# Gesture.net
KiCad netlist of a schematic drawn in EAGLE
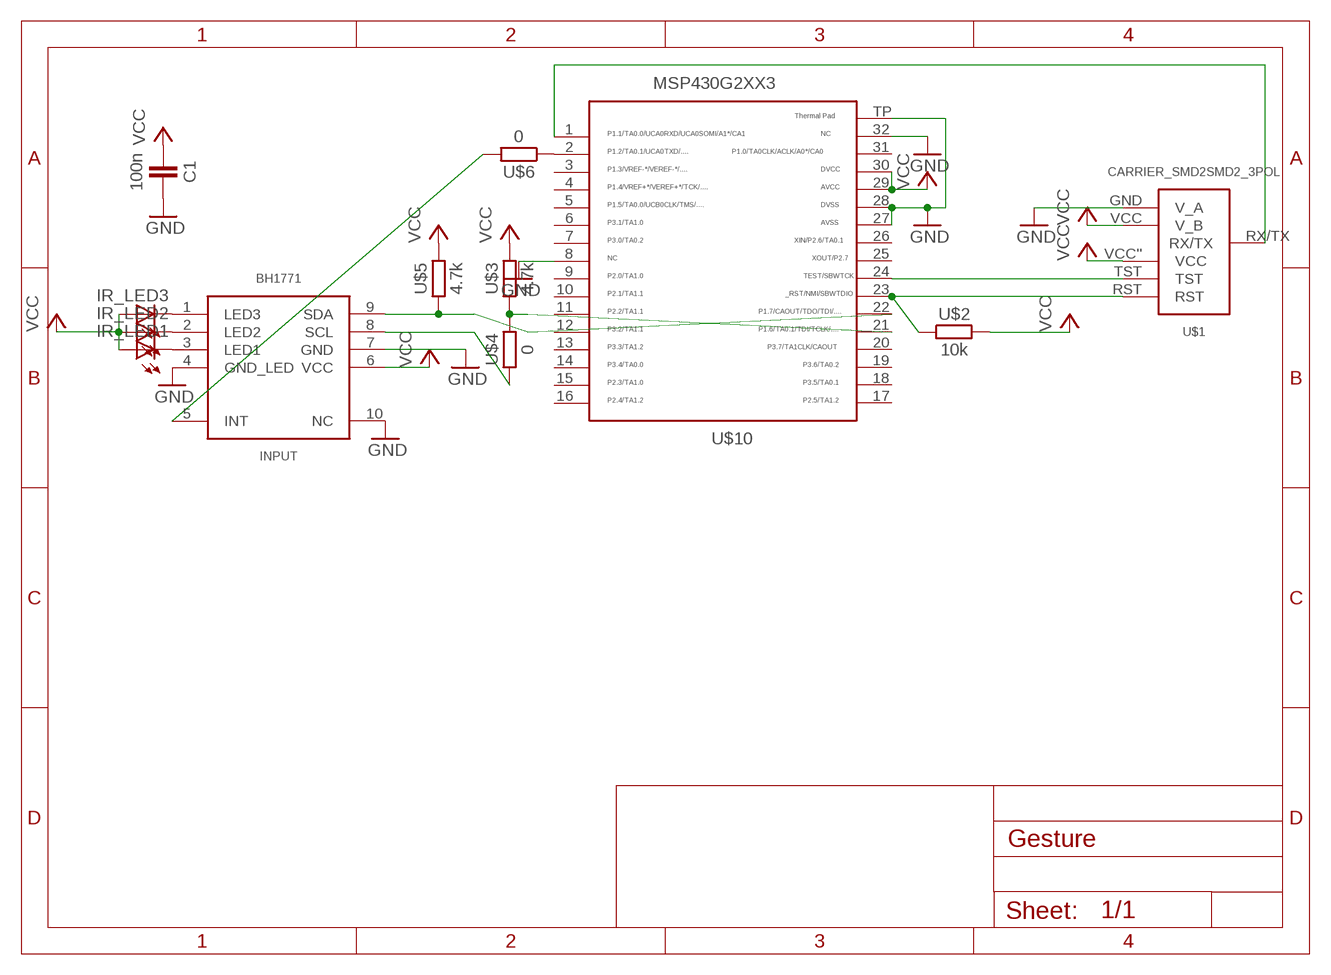
[diagram p0: schematic, sheet 1]

(export (version "E")
  (design (tool "Eeschema 10.0.6"))
  (components
    (comp (ref "C1")
      (value "100n")
      (footprint "eagle-import:603")
      (libsource (lib "eagle-import") (part "CAPACITOR"))
    )
    (comp (ref "INPUT")
      (value "BH1771")
      (footprint "eagle-import:BH1771")
      (libsource (lib "eagle-import") (part "BH1771"))
    )
    (comp (ref "IR_LED1")
      (value "LEDCHIP-LED0603")
      (footprint "eagle-import:CHIP-LED0603")
      (libsource (lib "eagle-import") (part "LEDCHIP-LED0603"))
    )
    (comp (ref "IR_LED2")
      (value "LEDCHIP-LED0603")
      (footprint "eagle-import:CHIP-LED0603")
      (libsource (lib "eagle-import") (part "LEDCHIP-LED0603"))
    )
    (comp (ref "IR_LED3")
      (value "LEDCHIP-LED0603")
      (footprint "eagle-import:CHIP-LED0603")
      (libsource (lib "eagle-import") (part "LEDCHIP-LED0603"))
    )
    (comp (ref "U$1")
      (value "CARRIER_SMD2SMD2_3POL")
      (footprint "eagle-import:CARRIER_SMD2_3POL")
      (libsource (lib "eagle-import") (part "CARRIER_SMD2SMD2_3POL"))
    )
    (comp (ref "U$2")
      (value "10k")
      (footprint "eagle-import:603")
      (libsource (lib "eagle-import") (part "RESISTOR0603"))
    )
    (comp (ref "U$3")
      (value "4.7k")
      (footprint "eagle-import:603")
      (libsource (lib "eagle-import") (part "RESISTOR0603"))
    )
    (comp (ref "U$4")
      (value "0")
      (footprint "eagle-import:603")
      (libsource (lib "eagle-import") (part "RESISTOR0603"))
    )
    (comp (ref "U$5")
      (value "4.7k")
      (footprint "eagle-import:603")
      (libsource (lib "eagle-import") (part "RESISTOR0603"))
    )
    (comp (ref "U$6")
      (value "0")
      (footprint "eagle-import:603")
      (libsource (lib "eagle-import") (part "RESISTOR0603"))
    )
    (comp (ref "U$10")
      (value "MSP430G2553")
      (footprint "eagle-import:QFN32")
      (libsource (lib "eagle-import") (part "MSP430G2553"))
    )
  )
  (nets
    (net (code "1") (name "GND") (class "Default")
      (node (ref "C1") (pin "2") (pinfunction "2_2") (pintype "passive"))
      (node (ref "INPUT") (pin "10") (pinfunction "NC_10") (pintype "bidirectional"))
      (node (ref "INPUT") (pin "4") (pinfunction "GND_LED_4") (pintype "bidirectional"))
      (node (ref "INPUT") (pin "7") (pinfunction "GND_7") (pintype "bidirectional"))
      (node (ref "U$1") (pin "GND") (pinfunction "V_A_GND") (pintype "bidirectional"))
      (node (ref "U$10") (pin "27") (pinfunction "27_27") (pintype "bidirectional"))
      (node (ref "U$10") (pin "28") (pinfunction "28_28") (pintype "bidirectional"))
      (node (ref "U$10") (pin "32") (pinfunction "32_32") (pintype "bidirectional"))
      (node (ref "U$10") (pin "8") (pinfunction "8_8") (pintype "bidirectional"))
      (node (ref "U$10") (pin "TP") (pinfunction "TP_TP") (pintype "bidirectional"))
    )
    (net (code "2") (name "Net-(INPUT-INT)") (class "Default")
      (node (ref "INPUT") (pin "5") (pinfunction "INT_5") (pintype "bidirectional"))
      (node (ref "U$6") (pin "2") (pinfunction "2_2") (pintype "passive"))
    )
    (net (code "3") (name "Net-(INPUT-LED1)") (class "Default")
      (node (ref "INPUT") (pin "3") (pinfunction "LED1_3") (pintype "bidirectional"))
      (node (ref "IR_LED1") (pin "C") (pinfunction "C_C") (pintype "passive"))
    )
    (net (code "4") (name "Net-(INPUT-LED2)") (class "Default")
      (node (ref "INPUT") (pin "2") (pinfunction "LED2_2") (pintype "bidirectional"))
      (node (ref "IR_LED2") (pin "C") (pinfunction "C_C") (pintype "passive"))
    )
    (net (code "5") (name "Net-(INPUT-LED3)") (class "Default")
      (node (ref "INPUT") (pin "1") (pinfunction "LED3_1") (pintype "bidirectional"))
      (node (ref "IR_LED3") (pin "C") (pinfunction "C_C") (pintype "passive"))
    )
    (net (code "6") (name "Net-(INPUT-SCL)") (class "Default")
      (node (ref "INPUT") (pin "8") (pinfunction "SCL_8") (pintype "bidirectional"))
      (node (ref "U$4") (pin "1") (pinfunction "1_1") (pintype "passive"))
    )
    (net (code "7") (name "Net-(INPUT-SDA)") (class "Default")
      (node (ref "INPUT") (pin "9") (pinfunction "SDA_9") (pintype "bidirectional"))
      (node (ref "U$10") (pin "22") (pinfunction "22_22") (pintype "bidirectional"))
      (node (ref "U$5") (pin "1") (pinfunction "1_1") (pintype "passive"))
    )
    (net (code "8") (name "Net-(U$1-PadRST)") (class "Default")
      (node (ref "U$1") (pin "RST") (pinfunction "RST_RST") (pintype "bidirectional"))
      (node (ref "U$10") (pin "23") (pinfunction "23_23") (pintype "bidirectional"))
      (node (ref "U$2") (pin "1") (pinfunction "1_1") (pintype "passive"))
    )
    (net (code "9") (name "Net-(U$1-PadRX{slash}TX)") (class "Default")
      (node (ref "U$1") (pin "RX/TX") (pinfunction "RX/TX_RX/TX") (pintype "bidirectional"))
      (node (ref "U$10") (pin "1") (pinfunction "1_1") (pintype "bidirectional"))
    )
    (net (code "10") (name "Net-(U$1-PadTST)") (class "Default")
      (node (ref "U$1") (pin "TST") (pinfunction "TST_TST") (pintype "bidirectional"))
      (node (ref "U$10") (pin "24") (pinfunction "24_24") (pintype "bidirectional"))
    )
    (net (code "11") (name "Net-(U$10-Pad2)") (class "Default")
      (node (ref "U$10") (pin "2") (pinfunction "2_2") (pintype "bidirectional"))
      (node (ref "U$6") (pin "1") (pinfunction "1_1") (pintype "passive"))
    )
    (net (code "12") (name "Net-(U$10-Pad21)") (class "Default")
      (node (ref "U$10") (pin "21") (pinfunction "21_21") (pintype "bidirectional"))
      (node (ref "U$3") (pin "1") (pinfunction "1_1") (pintype "passive"))
      (node (ref "U$4") (pin "2") (pinfunction "2_2") (pintype "passive"))
    )
    (net (code "13") (name "VCC") (class "Default")
      (node (ref "C1") (pin "1") (pinfunction "1_1") (pintype "passive"))
      (node (ref "INPUT") (pin "6") (pinfunction "VCC_6") (pintype "bidirectional"))
      (node (ref "IR_LED1") (pin "A") (pinfunction "A_A") (pintype "passive"))
      (node (ref "IR_LED2") (pin "A") (pinfunction "A_A") (pintype "passive"))
      (node (ref "IR_LED3") (pin "A") (pinfunction "A_A") (pintype "passive"))
      (node (ref "U$1") (pin "VCC") (pinfunction "V_B_VCC") (pintype "bidirectional"))
      (node (ref "U$1") (pin "VCC''") (pinfunction "VCC_VCC''") (pintype "bidirectional"))
      (node (ref "U$10") (pin "29") (pinfunction "29_29") (pintype "bidirectional"))
      (node (ref "U$10") (pin "30") (pinfunction "30_30") (pintype "bidirectional"))
      (node (ref "U$2") (pin "2") (pinfunction "2_2") (pintype "passive"))
      (node (ref "U$3") (pin "2") (pinfunction "2_2") (pintype "passive"))
      (node (ref "U$5") (pin "2") (pinfunction "2_2") (pintype "passive"))
    )
    (net (code "14") (name "unconnected-(U$10-Pad3)") (class "Default")
      (node (ref "U$10") (pin "3") (pinfunction "3_3") (pintype "bidirectional"))
    )
    (net (code "15") (name "unconnected-(U$10-Pad4)") (class "Default")
      (node (ref "U$10") (pin "4") (pinfunction "4_4") (pintype "bidirectional"))
    )
    (net (code "16") (name "unconnected-(U$10-Pad5)") (class "Default")
      (node (ref "U$10") (pin "5") (pinfunction "5_5") (pintype "bidirectional"))
    )
    (net (code "17") (name "unconnected-(U$10-Pad6)") (class "Default")
      (node (ref "U$10") (pin "6") (pinfunction "6_6") (pintype "bidirectional"))
    )
    (net (code "18") (name "unconnected-(U$10-Pad7)") (class "Default")
      (node (ref "U$10") (pin "7") (pinfunction "7_7") (pintype "bidirectional"))
    )
    (net (code "19") (name "unconnected-(U$10-Pad9)") (class "Default")
      (node (ref "U$10") (pin "9") (pinfunction "9_9") (pintype "bidirectional"))
    )
    (net (code "20") (name "unconnected-(U$10-Pad10)") (class "Default")
      (node (ref "U$10") (pin "10") (pinfunction "10_10") (pintype "bidirectional"))
    )
    (net (code "21") (name "unconnected-(U$10-Pad11)") (class "Default")
      (node (ref "U$10") (pin "11") (pinfunction "11_11") (pintype "bidirectional"))
    )
    (net (code "22") (name "unconnected-(U$10-Pad12)") (class "Default")
      (node (ref "U$10") (pin "12") (pinfunction "12_12") (pintype "bidirectional"))
    )
    (net (code "23") (name "unconnected-(U$10-Pad13)") (class "Default")
      (node (ref "U$10") (pin "13") (pinfunction "13_13") (pintype "bidirectional"))
    )
    (net (code "24") (name "unconnected-(U$10-Pad14)") (class "Default")
      (node (ref "U$10") (pin "14") (pinfunction "14_14") (pintype "bidirectional"))
    )
    (net (code "25") (name "unconnected-(U$10-Pad15)") (class "Default")
      (node (ref "U$10") (pin "15") (pinfunction "15_15") (pintype "bidirectional"))
    )
    (net (code "26") (name "unconnected-(U$10-Pad16)") (class "Default")
      (node (ref "U$10") (pin "16") (pinfunction "16_16") (pintype "bidirectional"))
    )
    (net (code "27") (name "unconnected-(U$10-Pad17)") (class "Default")
      (node (ref "U$10") (pin "17") (pinfunction "17_17") (pintype "bidirectional"))
    )
    (net (code "28") (name "unconnected-(U$10-Pad18)") (class "Default")
      (node (ref "U$10") (pin "18") (pinfunction "18_18") (pintype "bidirectional"))
    )
    (net (code "29") (name "unconnected-(U$10-Pad19)") (class "Default")
      (node (ref "U$10") (pin "19") (pinfunction "19_19") (pintype "bidirectional"))
    )
    (net (code "30") (name "unconnected-(U$10-Pad20)") (class "Default")
      (node (ref "U$10") (pin "20") (pinfunction "20_20") (pintype "bidirectional"))
    )
    (net (code "31") (name "unconnected-(U$10-Pad25)") (class "Default")
      (node (ref "U$10") (pin "25") (pinfunction "25_25") (pintype "bidirectional"))
    )
    (net (code "32") (name "unconnected-(U$10-Pad26)") (class "Default")
      (node (ref "U$10") (pin "26") (pinfunction "26_26") (pintype "bidirectional"))
    )
    (net (code "33") (name "unconnected-(U$10-Pad31)") (class "Default")
      (node (ref "U$10") (pin "31") (pinfunction "31_31") (pintype "bidirectional"))
    )
  )
)
